# ShutdownLoop.net
KiCad netlist of a schematic drawn in Altium Designer
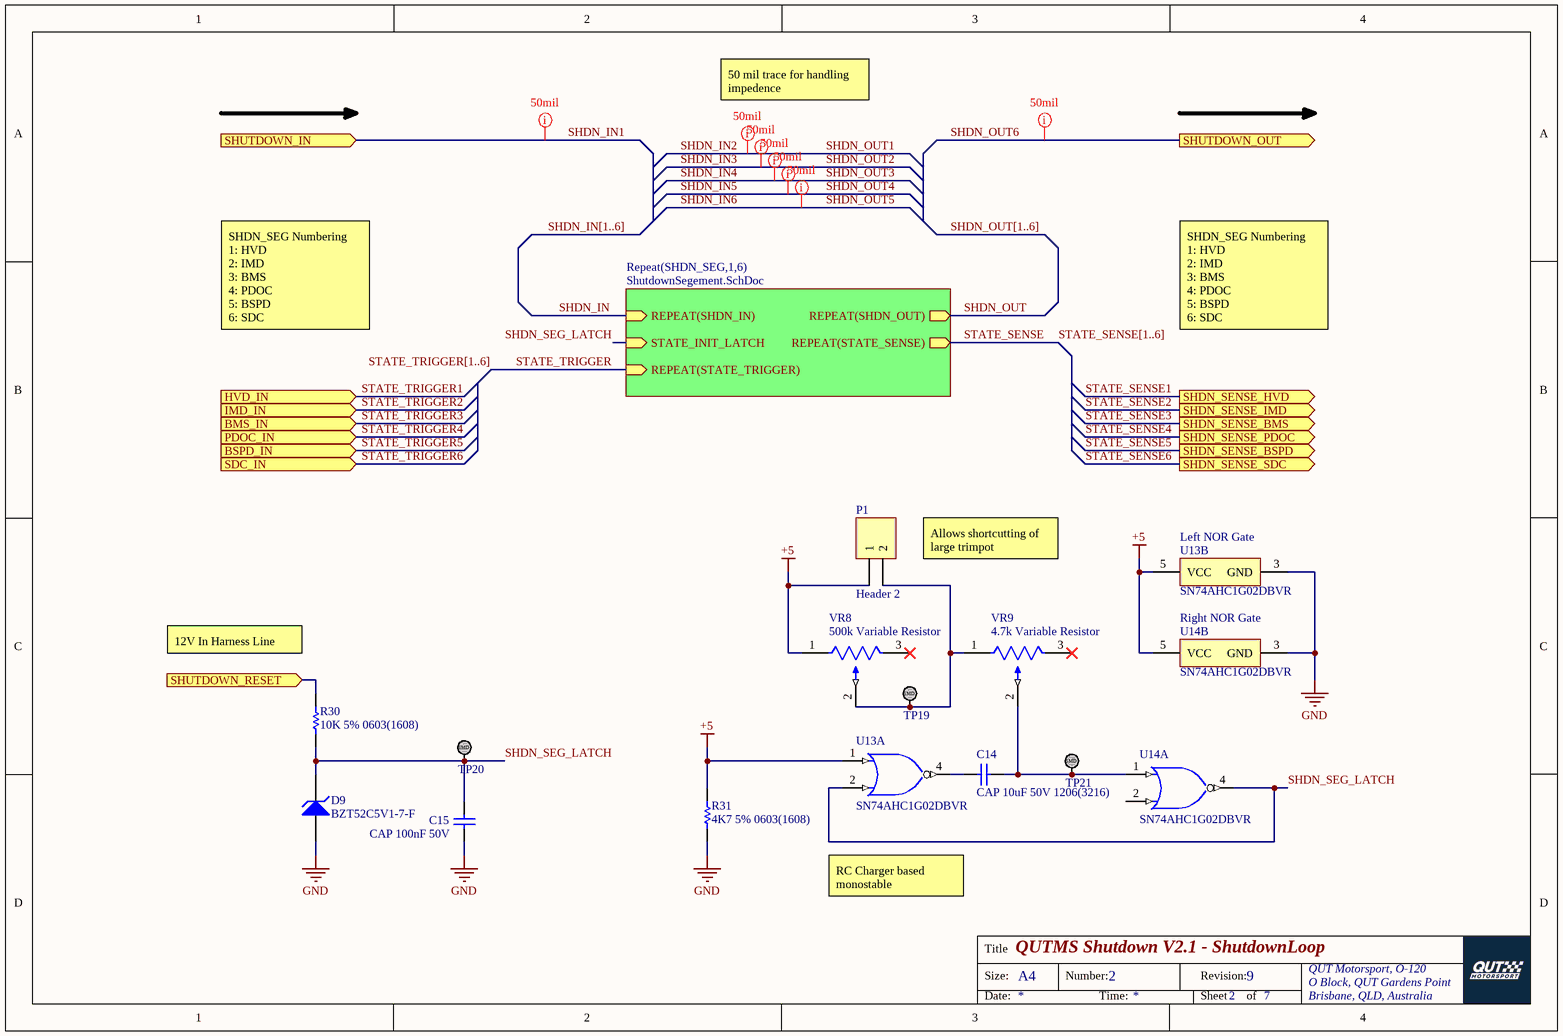
[diagram p0: ShutdownLoop.SchDoc]

(export (version "E")
  (design (tool "Eeschema 10.0.6"))
  (components
    (comp (ref "C14")
      (value "CAP 10uF 50V 1206(3216)")
      (footprint "CAPC1206(3216)190_M")
      (description "CAP 10uF 50V ±10% 1206 (3216 Metric) Thickness 1.9mm SMD")
      (fields (field (name "TOLERANCE") "Â±10%"))
      (libsource (lib "Altium Content Vault") (part "CAP"))
    )
    (comp (ref "C15")
      (value "CAP 100nF 50V")
      (footprint "CAPC0603(1608)100_L")
      (description "CAP 100nF 50V ±5% 0603 (1608 Metric) Thickness 1mm SMD")
      (fields (field (name "TOLERANCE") "Â±5%"))
      (libsource (lib "Altium Content Vault") (part "CAP"))
    )
    (comp (ref "D9")
      (value "BZT52C5V1-7-F")
      (footprint "DIOD-SOD123_V")
      (description "Surface Mount Zener Diode, 5.1 V, -65 to 150 degC, 2-Pin SMD (SOD-123), RoHS, Tape and Reel")
      (fields (field (name "MANUFACTURER") "DiodesIncorporated"))
      (libsource (lib "Altium Content Vault") (part "DZEN-AK-2"))
    )
    (comp (ref "P1")
      (value "Header 2")
      (footprint "HDR1X2")
      (description "Header, 2-Pin")
      (fields (field (name "PUBLISHER") "Altium Limited"))
      (libsource (lib "Miscellaneous Connectors") (part "Header 2"))
    )
    (comp (ref "R30")
      (value "10K 5% 0603(1608)")
      (footprint "RESC0603(1608)_N")
      (description "10K 0.1W 5% 0603 (1608 Metric)  SMD")
      (fields (field (name "TOLERANCE") "5 %") (field (name "POWER") "0.1 W"))
      (libsource (lib "Altium Content Vault") (part "RES"))
    )
    (comp (ref "R31")
      (value "4K7 5% 0603(1608)")
      (footprint "RESC0603(1608)_N")
      (description "4K7 0.1W 5% 0603 (1608 Metric)  SMD")
      (fields (field (name "TOLERANCE") "5 %") (field (name "POWER") "0.1 W"))
      (libsource (lib "Altium Content Vault") (part "RES"))
    )
    (comp (ref "TP19")
      (value "TestPoint_SMD")
      (footprint "TestPointSMD")
      (libsource (lib "StandardTest") (part "TestPoint_SMD"))
    )
    (comp (ref "TP20")
      (value "TestPoint_SMD")
      (footprint "TestPointSMD")
      (libsource (lib "StandardTest") (part "TestPoint_SMD"))
    )
    (comp (ref "TP21")
      (value "TestPoint_SMD")
      (footprint "TestPointSMD")
      (libsource (lib "StandardTest") (part "TestPoint_SMD"))
    )
    (comp (ref "U13")
      (value "SN74AHC1G02DBVR")
      (footprint "DBV0005A_L")
      (description "Single 2-Input Positive-NOR Gate, DBV0005A, LARGE T&R")
      (fields
        (field (name "MANUFACTURER") "Texas Instruments")
        (field (name "GENERIC PART NUMBER") "SN74AHC1G02")
      )
      (libsource (lib "Altium Content Vault") (part "TI-SN74XXX1X02-5"))
    )
    (comp (ref "U14")
      (value "SN74AHC1G02DBVR")
      (footprint "DBV0005A_L")
      (description "Single 2-Input Positive-NOR Gate, DBV0005A, LARGE T&R")
      (fields
        (field (name "MANUFACTURER") "Texas Instruments")
        (field (name "GENERIC PART NUMBER") "SN74AHC1G02")
      )
      (libsource (lib "Altium Content Vault") (part "TI-SN74XXX1X02-5"))
    )
    (comp (ref "VR8")
      (value "500k Variable Resistor")
      (footprint "VG039NCHXTB472")
      (description "500K ±25% ±250 ppm/°C SMD Variable Resistors RoHS ¦ VG039NCHXTB504")
      (libsource (lib "QUTMS_PotentiometerLibrary") (part "500k Variable Resistor"))
    )
    (comp (ref "VR9")
      (value "4.7k Variable Resistor")
      (footprint "VG039NCHXTB472")
      (description "4k7 ±25% ±250 ppm/°C SMD Variable Resistors RoHS ¦ VG039NCHXTB472")
      (libsource (lib "QUTMS_PotentiometerLibrary") (part "4.7k Variable Resistor"))
    )
  )
  (nets
    (net (code "1") (name "+5") (class "Default")
      (node (ref "P1") (pin "1") (pinfunction "1_1") (pintype "passive"))
      (node (ref "R31") (pin "2") (pinfunction "2_2") (pintype "passive"))
      (node (ref "U13") (pin "1") (pinfunction "A_1") (pintype "input"))
      (node (ref "U13") (pin "5") (pinfunction "VCC_5") (pintype "power_in"))
      (node (ref "U14") (pin "5") (pinfunction "VCC_5") (pintype "power_in"))
      (node (ref "VR8") (pin "1") (pinfunction "48_1") (pintype "passive"))
    )
    (net (code "13") (name "/SHDN_SEG_LATCH") (class "Default")
      (node (ref "C15") (pin "1") (pinfunction "1_1") (pintype "passive"))
      (node (ref "D9") (pin "2") (pinfunction "K_2") (pintype "passive"))
      (node (ref "R30") (pin "2") (pinfunction "2_2") (pintype "passive"))
      (node (ref "TP20") (pin "1") (pinfunction "1_1") (pintype "passive"))
      (node (ref "U13") (pin "2") (pinfunction "B_2") (pintype "input"))
      (node (ref "U14") (pin "4") (pinfunction "Y_4") (pintype "output"))
    )
    (net (code "14") (name "/SHUTDOWN_RESET") (class "Default")
      (node (ref "R30") (pin "1") (pinfunction "1_1") (pintype "passive"))
    )
    (net (code "31") (name "GND") (class "Default")
      (node (ref "C15") (pin "2") (pinfunction "2_2") (pintype "passive"))
      (node (ref "D9") (pin "1") (pinfunction "A_1") (pintype "passive"))
      (node (ref "R31") (pin "1") (pinfunction "1_1") (pintype "passive"))
      (node (ref "U13") (pin "3") (pinfunction "GND_3") (pintype "power_in"))
      (node (ref "U14") (pin "3") (pinfunction "GND_3") (pintype "power_in"))
    )
    (net (code "32") (name "Net-(U13A-Y)") (class "Default")
      (node (ref "C14") (pin "2") (pinfunction "2_2") (pintype "passive"))
      (node (ref "U13") (pin "4") (pinfunction "Y_4") (pintype "output"))
    )
    (net (code "33") (name "Net-(U14A-A)") (class "Default")
      (node (ref "C14") (pin "1") (pinfunction "1_1") (pintype "passive"))
      (node (ref "TP21") (pin "1") (pinfunction "1_1") (pintype "passive"))
      (node (ref "U14") (pin "1") (pinfunction "A_1") (pintype "input"))
      (node (ref "VR9") (pin "2") (pinfunction "50_2") (pintype "output"))
    )
    (net (code "34") (name "Net-(VR8-50)") (class "Default")
      (node (ref "P1") (pin "2") (pinfunction "2_2") (pintype "passive"))
      (node (ref "TP19") (pin "1") (pinfunction "1_1") (pintype "passive"))
      (node (ref "VR8") (pin "2") (pinfunction "50_2") (pintype "output"))
      (node (ref "VR9") (pin "1") (pinfunction "48_1") (pintype "passive"))
    )
    (net (code "35") (name "unconnected-(U14A-B-Pad2)") (class "Default")
      (node (ref "U14") (pin "2") (pinfunction "B_2") (pintype "input"))
    )
    (net (code "36") (name "unconnected-(VR8-49-Pad3)") (class "Default")
      (node (ref "VR8") (pin "3") (pinfunction "49_3") (pintype "passive+no_connect"))
    )
    (net (code "37") (name "unconnected-(VR9-49-Pad3)") (class "Default")
      (node (ref "VR9") (pin "3") (pinfunction "49_3") (pintype "passive+no_connect"))
    )
  )
)
